# SwitchDaughter.net
KiCad netlist of a schematic drawn in Altium Designer
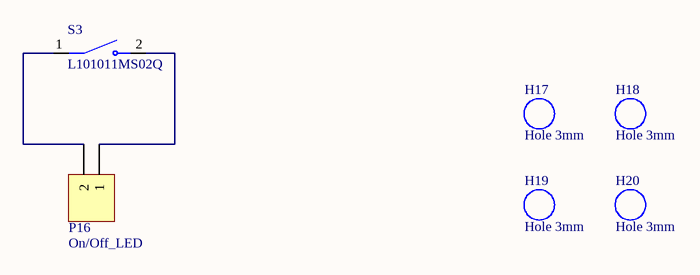
[diagram p0: SwitchDaughter.SchDoc]

(export (version "E")
  (design (tool "Eeschema 10.0.6"))
  (components
    (comp (ref "H17")
      (value "Hole 3mm")
      (footprint "Hole 3mm")
      (libsource (lib "ECE Lib 22") (part "Hole 3mm"))
    )
    (comp (ref "H18")
      (value "Hole 3mm")
      (footprint "Hole 3mm")
      (libsource (lib "ECE Lib 22") (part "Hole 3mm"))
    )
    (comp (ref "H19")
      (value "Hole 3mm")
      (footprint "Hole 3mm")
      (libsource (lib "ECE Lib 22") (part "Hole 3mm"))
    )
    (comp (ref "H20")
      (value "Hole 3mm")
      (footprint "Hole 3mm")
      (libsource (lib "ECE Lib 22") (part "Hole 3mm"))
    )
    (comp (ref "P16")
      (value "On/Off_LED")
      (footprint "HDR1X2")
      (description "Header, 2-Pin, Right Angle")
      (fields (field (name "PUBLISHER") "Altium Limited"))
      (libsource (lib "Miscellaneous Connectors") (part "Header 2H"))
    )
    (comp (ref "S3")
      (value "L101011MS02Q")
      (footprint "SW_L101011MS02Q")
      (description "Slide Switch SPST Through Hole")
      (fields (field (name "MF") "C&K"))
      (libsource (lib "L101011MS02Q") (part "L101011MS02Q"))
    )
  )
  (nets
    (net (code "1") (name "Net-(P16-Pad1)") (class "Default")
      (node (ref "P16") (pin "1") (pinfunction "1_1") (pintype "passive"))
      (node (ref "S3") (pin "2") (pinfunction "2_2") (pintype "passive"))
    )
    (net (code "2") (name "Net-(P16-Pad2)") (class "Default")
      (node (ref "P16") (pin "2") (pinfunction "2_2") (pintype "passive"))
      (node (ref "S3") (pin "1") (pinfunction "1_1") (pintype "passive"))
    )
  )
)
